# Motorcontroller.net
KiCad netlist of a schematic drawn in Altium Designer
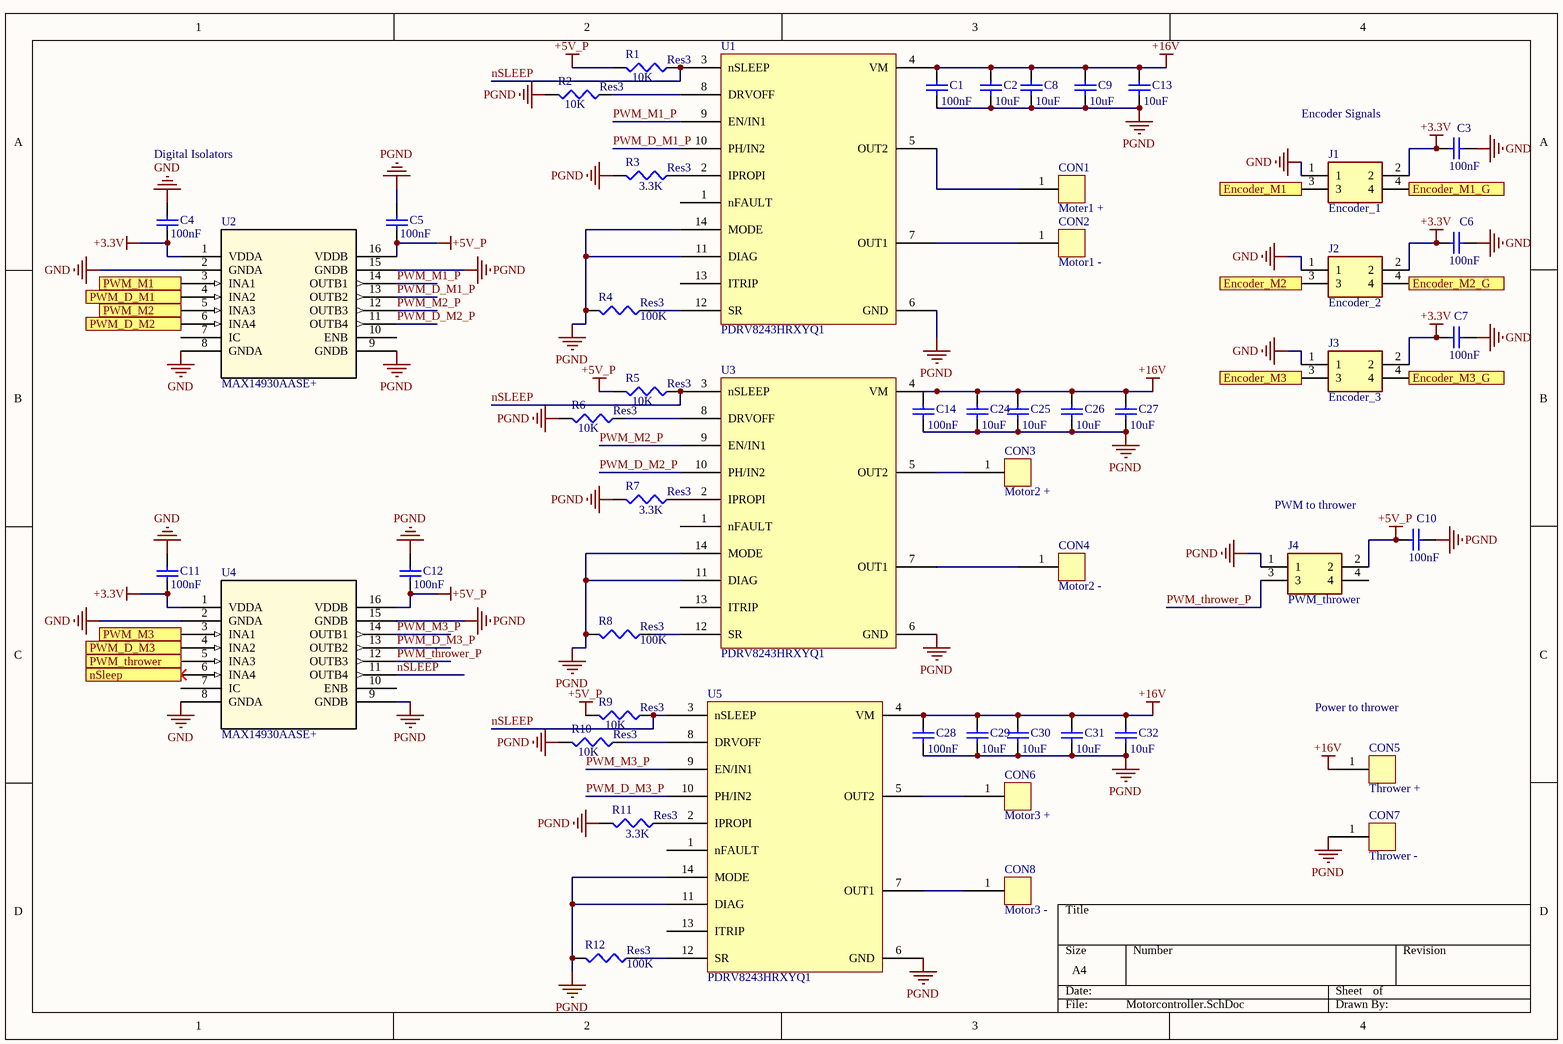
[diagram p0: Motorcontroller.SchDoc]

(export (version "E")
  (design (tool "Eeschema 10.0.6"))
  (components
    (comp (ref "C1")
      (value "100nF")
      (footprint "1608[0603]")
      (description "Capacitor (Semiconductor SIM Model)")
      (fields (field (name "Comment") "Cap Semi") (field (name "PUBLISHER") "Altium Limited"))
      (libsource (lib "Miscellaneous Devices") (part "Cap Semi"))
    )
    (comp (ref "C2")
      (value "10uF")
      (footprint "C1206")
      (description "Capacitor (Semiconductor SIM Model)")
      (fields (field (name "Comment") "Cap Semi") (field (name "PUBLISHER") "Altium Limited"))
      (libsource (lib "Miscellaneous Devices") (part "Cap Semi"))
    )
    (comp (ref "C3")
      (value "100nF")
      (footprint "1608[0603]")
      (description "Capacitor (Semiconductor SIM Model)")
      (fields (field (name "Comment") "Cap Semi") (field (name "PUBLISHER") "Altium Limited"))
      (libsource (lib "Miscellaneous Devices") (part "Cap Semi"))
    )
    (comp (ref "C4")
      (value "100nF")
      (footprint "1608[0603]")
      (description "Capacitor (Semiconductor SIM Model)")
      (fields (field (name "Comment") "Cap Semi") (field (name "PUBLISHER") "Altium Limited"))
      (libsource (lib "") (part "Cap Semi_1"))
    )
    (comp (ref "C5")
      (value "100nF")
      (footprint "1608[0603]")
      (description "Capacitor (Semiconductor SIM Model)")
      (fields (field (name "Comment") "Cap Semi") (field (name "PUBLISHER") "Altium Limited"))
      (libsource (lib "") (part "Cap Semi_1"))
    )
    (comp (ref "C6")
      (value "100nF")
      (footprint "1608[0603]")
      (description "Capacitor (Semiconductor SIM Model)")
      (fields (field (name "Comment") "Cap Semi") (field (name "PUBLISHER") "Altium Limited"))
      (libsource (lib "Miscellaneous Devices") (part "Cap Semi"))
    )
    (comp (ref "C7")
      (value "100nF")
      (footprint "1608[0603]")
      (description "Capacitor (Semiconductor SIM Model)")
      (fields (field (name "Comment") "Cap Semi") (field (name "PUBLISHER") "Altium Limited"))
      (libsource (lib "Miscellaneous Devices") (part "Cap Semi"))
    )
    (comp (ref "C8")
      (value "10uF")
      (footprint "C1206")
      (description "Capacitor (Semiconductor SIM Model)")
      (fields (field (name "Comment") "Cap Semi") (field (name "PUBLISHER") "Altium Limited"))
      (libsource (lib "Miscellaneous Devices") (part "Cap Semi"))
    )
    (comp (ref "C9")
      (value "10uF")
      (footprint "C1206")
      (description "Capacitor (Semiconductor SIM Model)")
      (fields (field (name "Comment") "Cap Semi") (field (name "PUBLISHER") "Altium Limited"))
      (libsource (lib "Miscellaneous Devices") (part "Cap Semi"))
    )
    (comp (ref "C10")
      (value "100nF")
      (footprint "1608[0603]")
      (description "Capacitor (Semiconductor SIM Model)")
      (fields (field (name "Comment") "Cap Semi") (field (name "PUBLISHER") "Altium Limited"))
      (libsource (lib "Miscellaneous Devices") (part "Cap Semi"))
    )
    (comp (ref "C11")
      (value "100nF")
      (footprint "1608[0603]")
      (description "Capacitor (Semiconductor SIM Model)")
      (fields (field (name "Comment") "Cap Semi") (field (name "PUBLISHER") "Altium Limited"))
      (libsource (lib "") (part "Cap Semi_1"))
    )
    (comp (ref "C12")
      (value "100nF")
      (footprint "1608[0603]")
      (description "Capacitor (Semiconductor SIM Model)")
      (fields (field (name "Comment") "Cap Semi") (field (name "PUBLISHER") "Altium Limited"))
      (libsource (lib "") (part "Cap Semi_1"))
    )
    (comp (ref "C13")
      (value "10uF")
      (footprint "C1206")
      (description "Capacitor (Semiconductor SIM Model)")
      (fields (field (name "Comment") "Cap Semi") (field (name "PUBLISHER") "Altium Limited"))
      (libsource (lib "Miscellaneous Devices") (part "Cap Semi"))
    )
    (comp (ref "C14")
      (value "100nF")
      (footprint "1608[0603]")
      (description "Capacitor (Semiconductor SIM Model)")
      (fields (field (name "Comment") "Cap Semi") (field (name "PUBLISHER") "Altium Limited"))
      (libsource (lib "Miscellaneous Devices") (part "Cap Semi"))
    )
    (comp (ref "C24")
      (value "10uF")
      (footprint "C1206")
      (description "Capacitor (Semiconductor SIM Model)")
      (fields (field (name "Comment") "Cap Semi") (field (name "PUBLISHER") "Altium Limited"))
      (libsource (lib "Miscellaneous Devices") (part "Cap Semi"))
    )
    (comp (ref "C25")
      (value "10uF")
      (footprint "C1206")
      (description "Capacitor (Semiconductor SIM Model)")
      (fields (field (name "Comment") "Cap Semi") (field (name "PUBLISHER") "Altium Limited"))
      (libsource (lib "Miscellaneous Devices") (part "Cap Semi"))
    )
    (comp (ref "C26")
      (value "10uF")
      (footprint "C1206")
      (description "Capacitor (Semiconductor SIM Model)")
      (fields (field (name "Comment") "Cap Semi") (field (name "PUBLISHER") "Altium Limited"))
      (libsource (lib "Miscellaneous Devices") (part "Cap Semi"))
    )
    (comp (ref "C27")
      (value "10uF")
      (footprint "C1206")
      (description "Capacitor (Semiconductor SIM Model)")
      (fields (field (name "Comment") "Cap Semi") (field (name "PUBLISHER") "Altium Limited"))
      (libsource (lib "Miscellaneous Devices") (part "Cap Semi"))
    )
    (comp (ref "C28")
      (value "100nF")
      (footprint "1608[0603]")
      (description "Capacitor (Semiconductor SIM Model)")
      (fields (field (name "Comment") "Cap Semi") (field (name "PUBLISHER") "Altium Limited"))
      (libsource (lib "Miscellaneous Devices") (part "Cap Semi"))
    )
    (comp (ref "C29")
      (value "10uF")
      (footprint "C1206")
      (description "Capacitor (Semiconductor SIM Model)")
      (fields (field (name "Comment") "Cap Semi") (field (name "PUBLISHER") "Altium Limited"))
      (libsource (lib "Miscellaneous Devices") (part "Cap Semi"))
    )
    (comp (ref "C30")
      (value "10uF")
      (footprint "C1206")
      (description "Capacitor (Semiconductor SIM Model)")
      (fields (field (name "Comment") "Cap Semi") (field (name "PUBLISHER") "Altium Limited"))
      (libsource (lib "Miscellaneous Devices") (part "Cap Semi"))
    )
    (comp (ref "C31")
      (value "10uF")
      (footprint "C1206")
      (description "Capacitor (Semiconductor SIM Model)")
      (fields (field (name "Comment") "Cap Semi") (field (name "PUBLISHER") "Altium Limited"))
      (libsource (lib "Miscellaneous Devices") (part "Cap Semi"))
    )
    (comp (ref "C32")
      (value "10uF")
      (footprint "C1206")
      (description "Capacitor (Semiconductor SIM Model)")
      (fields (field (name "Comment") "Cap Semi") (field (name "PUBLISHER") "Altium Limited"))
      (libsource (lib "Miscellaneous Devices") (part "Cap Semi"))
    )
    (comp (ref "CON1")
      (value "Moter1 +")
      (footprint "con_soldering")
      (libsource (lib "con_soldering") (part "Con_soldering"))
    )
    (comp (ref "CON2")
      (value "Motor1 -")
      (footprint "con_soldering")
      (libsource (lib "con_soldering") (part "Con_soldering"))
    )
    (comp (ref "CON3")
      (value "Motor2 +")
      (footprint "con_soldering")
      (libsource (lib "con_soldering") (part "Con_soldering"))
    )
    (comp (ref "CON4")
      (value "Motor2 -")
      (footprint "con_soldering")
      (libsource (lib "con_soldering") (part "Con_soldering"))
    )
    (comp (ref "CON5")
      (value "Thrower +")
      (footprint "con_soldering")
      (libsource (lib "con_soldering") (part "Con_soldering"))
    )
    (comp (ref "CON6")
      (value "Motor3 +")
      (footprint "con_soldering")
      (libsource (lib "con_soldering") (part "Con_soldering"))
    )
    (comp (ref "CON7")
      (value "Thrower -")
      (footprint "con_soldering")
      (libsource (lib "con_soldering") (part "Con_soldering"))
    )
    (comp (ref "CON8")
      (value "Motor3 -")
      (footprint "con_soldering")
      (libsource (lib "con_soldering") (part "Con_soldering"))
    )
    (comp (ref "J1")
      (value "Encoder_1")
      (footprint "TE_7-215079-4:TE_7-215079-4")
      (description "Micro-MaTch 4 Position 1.27 mm Pitch Vertical Female-on-Board Connector")
      (fields (field (name "MP") "7-215079-4") (field (name "MF") "TE Connectivity"))
      (libsource (lib "Con_encoder_4") (part "Con_4_encoder"))
    )
    (comp (ref "J2")
      (value "Encoder_2")
      (footprint "TE_7-215079-4:TE_7-215079-4")
      (description "Micro-MaTch 4 Position 1.27 mm Pitch Vertical Female-on-Board Connector")
      (fields (field (name "MP") "7-215079-4") (field (name "MF") "TE Connectivity"))
      (libsource (lib "Con_encoder_4") (part "Con_4_encoder"))
    )
    (comp (ref "J3")
      (value "Encoder_3")
      (footprint "TE_7-215079-4:TE_7-215079-4")
      (description "Micro-MaTch 4 Position 1.27 mm Pitch Vertical Female-on-Board Connector")
      (fields (field (name "MP") "7-215079-4") (field (name "MF") "TE Connectivity"))
      (libsource (lib "Con_encoder_4") (part "Con_4_encoder"))
    )
    (comp (ref "J4")
      (value "PWM_thrower")
      (footprint "TE_7-215079-4:TE_7-215079-4")
      (description "Micro-MaTch 4 Position 1.27 mm Pitch Vertical Female-on-Board Connector")
      (fields (field (name "MP") "7-215079-4") (field (name "MF") "TE Connectivity"))
      (libsource (lib "Con_encoder_4") (part "Con_4_encoder"))
    )
    (comp (ref "R1")
      (value "Res3")
      (footprint "J1-0603")
      (description "Resistor")
      (fields (field (name "ALTIUM_VALUE") "10K") (field (name "PUBLISHER") "Altium Limited"))
      (libsource (lib "Miscellaneous Devices") (part "Res3"))
    )
    (comp (ref "R2")
      (value "Res3")
      (footprint "J1-0603")
      (description "Resistor")
      (fields (field (name "ALTIUM_VALUE") "10K") (field (name "PUBLISHER") "Altium Limited"))
      (libsource (lib "Miscellaneous Devices") (part "Res3"))
    )
    (comp (ref "R3")
      (value "Res3")
      (footprint "J1-0603")
      (description "Resistor")
      (fields (field (name "ALTIUM_VALUE") "3.3K") (field (name "PUBLISHER") "Altium Limited"))
      (libsource (lib "Miscellaneous Devices") (part "Res3"))
    )
    (comp (ref "R4")
      (value "Res3")
      (footprint "J1-0603")
      (description "Resistor")
      (fields (field (name "ALTIUM_VALUE") "100K") (field (name "PUBLISHER") "Altium Limited"))
      (libsource (lib "Miscellaneous Devices") (part "Res3"))
    )
    (comp (ref "R5")
      (value "Res3")
      (footprint "J1-0603")
      (description "Resistor")
      (fields (field (name "ALTIUM_VALUE") "10K") (field (name "PUBLISHER") "Altium Limited"))
      (libsource (lib "Miscellaneous Devices") (part "Res3"))
    )
    (comp (ref "R6")
      (value "Res3")
      (footprint "J1-0603")
      (description "Resistor")
      (fields (field (name "ALTIUM_VALUE") "10K") (field (name "PUBLISHER") "Altium Limited"))
      (libsource (lib "Miscellaneous Devices") (part "Res3"))
    )
    (comp (ref "R7")
      (value "Res3")
      (footprint "J1-0603")
      (description "Resistor")
      (fields (field (name "ALTIUM_VALUE") "3.3K") (field (name "PUBLISHER") "Altium Limited"))
      (libsource (lib "Miscellaneous Devices") (part "Res3"))
    )
    (comp (ref "R8")
      (value "Res3")
      (footprint "J1-0603")
      (description "Resistor")
      (fields (field (name "ALTIUM_VALUE") "100K") (field (name "PUBLISHER") "Altium Limited"))
      (libsource (lib "Miscellaneous Devices") (part "Res3"))
    )
    (comp (ref "R9")
      (value "Res3")
      (footprint "J1-0603")
      (description "Resistor")
      (fields (field (name "ALTIUM_VALUE") "10K") (field (name "PUBLISHER") "Altium Limited"))
      (libsource (lib "Miscellaneous Devices") (part "Res3"))
    )
    (comp (ref "R10")
      (value "Res3")
      (footprint "J1-0603")
      (description "Resistor")
      (fields (field (name "ALTIUM_VALUE") "10K") (field (name "PUBLISHER") "Altium Limited"))
      (libsource (lib "Miscellaneous Devices") (part "Res3"))
    )
    (comp (ref "R11")
      (value "Res3")
      (footprint "J1-0603")
      (description "Resistor")
      (fields (field (name "ALTIUM_VALUE") "3.3K") (field (name "PUBLISHER") "Altium Limited"))
      (libsource (lib "Miscellaneous Devices") (part "Res3"))
    )
    (comp (ref "R12")
      (value "Res3")
      (footprint "J1-0603")
      (description "Resistor")
      (fields (field (name "ALTIUM_VALUE") "100K") (field (name "PUBLISHER") "Altium Limited"))
      (libsource (lib "Miscellaneous Devices") (part "Res3"))
    )
    (comp (ref "U1")
      (value "PDRV8243HRXYQ1")
      (footprint "DRV8243_motor_driver")
      (libsource (lib "DRV8243-Q1") (part "PDRV8243HRXYQ1"))
    )
    (comp (ref "U2")
      (value "MAX14930AASE+")
      (footprint "21-0041_S16+1_MXM")
      (description "No Description Available")
      (fields (field (name "COPYRIGHT") "Copyright (C) 2021 Ultra Librarian. All rights reserved."))
      (libsource (lib "MAX14930AASE&plus_") (part "MAX14930AASE+"))
    )
    (comp (ref "U3")
      (value "PDRV8243HRXYQ1")
      (footprint "DRV8243_motor_driver")
      (libsource (lib "DRV8243-Q1") (part "PDRV8243HRXYQ1"))
    )
    (comp (ref "U4")
      (value "MAX14930AASE+")
      (footprint "21-0041_S16+1_MXM")
      (description "No Description Available")
      (fields (field (name "COPYRIGHT") "Copyright (C) 2021 Ultra Librarian. All rights reserved."))
      (libsource (lib "MAX14930AASE&plus_") (part "MAX14930AASE+"))
    )
    (comp (ref "U5")
      (value "PDRV8243HRXYQ1")
      (footprint "DRV8243_motor_driver")
      (libsource (lib "DRV8243-Q1") (part "PDRV8243HRXYQ1"))
    )
  )
  (nets
    (net (code "1") (name "+3.3V") (class "Default")
      (node (ref "C11") (pin "2") (pinfunction "2_2") (pintype "passive"))
      (node (ref "C3") (pin "2") (pinfunction "2_2") (pintype "passive"))
      (node (ref "C4") (pin "2") (pinfunction "2_2") (pintype "passive"))
      (node (ref "C6") (pin "2") (pinfunction "2_2") (pintype "passive"))
      (node (ref "C7") (pin "2") (pinfunction "2_2") (pintype "passive"))
      (node (ref "J1") (pin "2") (pinfunction "2_2") (pintype "passive"))
      (node (ref "J2") (pin "2") (pinfunction "2_2") (pintype "passive"))
      (node (ref "J3") (pin "2") (pinfunction "2_2") (pintype "passive"))
      (node (ref "U2") (pin "1") (pinfunction "VDDA_1") (pintype "power_in"))
      (node (ref "U4") (pin "1") (pinfunction "VDDA_1") (pintype "power_in"))
    )
    (net (code "2") (name "+5V_P") (class "Default")
      (node (ref "C10") (pin "2") (pinfunction "2_2") (pintype "passive"))
      (node (ref "C12") (pin "2") (pinfunction "2_2") (pintype "passive"))
      (node (ref "C5") (pin "2") (pinfunction "2_2") (pintype "passive"))
      (node (ref "J4") (pin "2") (pinfunction "2_2") (pintype "passive"))
      (node (ref "R1") (pin "2") (pinfunction "2_2") (pintype "passive"))
      (node (ref "R5") (pin "2") (pinfunction "2_2") (pintype "passive"))
      (node (ref "R9") (pin "2") (pinfunction "2_2") (pintype "passive"))
      (node (ref "U2") (pin "16") (pinfunction "VDDB_16") (pintype "power_in"))
      (node (ref "U4") (pin "16") (pinfunction "VDDB_16") (pintype "power_in"))
    )
    (net (code "3") (name "+16V") (class "Default")
      (node (ref "C1") (pin "2") (pinfunction "2_2") (pintype "passive"))
      (node (ref "C13") (pin "2") (pinfunction "2_2") (pintype "passive"))
      (node (ref "C14") (pin "2") (pinfunction "2_2") (pintype "passive"))
      (node (ref "C2") (pin "2") (pinfunction "2_2") (pintype "passive"))
      (node (ref "C24") (pin "2") (pinfunction "2_2") (pintype "passive"))
      (node (ref "C25") (pin "2") (pinfunction "2_2") (pintype "passive"))
      (node (ref "C26") (pin "2") (pinfunction "2_2") (pintype "passive"))
      (node (ref "C27") (pin "2") (pinfunction "2_2") (pintype "passive"))
      (node (ref "C28") (pin "2") (pinfunction "2_2") (pintype "passive"))
      (node (ref "C29") (pin "2") (pinfunction "2_2") (pintype "passive"))
      (node (ref "C30") (pin "2") (pinfunction "2_2") (pintype "passive"))
      (node (ref "C31") (pin "2") (pinfunction "2_2") (pintype "passive"))
      (node (ref "C32") (pin "2") (pinfunction "2_2") (pintype "passive"))
      (node (ref "C8") (pin "2") (pinfunction "2_2") (pintype "passive"))
      (node (ref "C9") (pin "2") (pinfunction "2_2") (pintype "passive"))
      (node (ref "CON5") (pin "1") (pintype "passive"))
      (node (ref "U1") (pin "4") (pinfunction "VM_4") (pintype "passive"))
      (node (ref "U3") (pin "4") (pinfunction "VM_4") (pintype "passive"))
      (node (ref "U5") (pin "4") (pinfunction "VM_4") (pintype "passive"))
    )
    (net (code "4") (name "/Encoder_M1") (class "Default")
      (node (ref "J1") (pin "3") (pinfunction "3_3") (pintype "passive"))
    )
    (net (code "5") (name "/Encoder_M1_G") (class "Default")
      (node (ref "J1") (pin "4") (pinfunction "4_4") (pintype "passive"))
    )
    (net (code "6") (name "/Encoder_M2") (class "Default")
      (node (ref "J2") (pin "3") (pinfunction "3_3") (pintype "passive"))
    )
    (net (code "7") (name "/Encoder_M2_G") (class "Default")
      (node (ref "J2") (pin "4") (pinfunction "4_4") (pintype "passive"))
    )
    (net (code "8") (name "/Encoder_M3") (class "Default")
      (node (ref "J3") (pin "3") (pinfunction "3_3") (pintype "passive"))
    )
    (net (code "9") (name "/Encoder_M3_G") (class "Default")
      (node (ref "J3") (pin "4") (pinfunction "4_4") (pintype "passive"))
    )
    (net (code "10") (name "/PWM_D_M1") (class "Default")
      (node (ref "U2") (pin "4") (pinfunction "INA2_4") (pintype "input"))
    )
    (net (code "11") (name "/PWM_D_M1_P") (class "Default")
      (node (ref "U1") (pin "10") (pinfunction "PH/IN2_10") (pintype "passive"))
      (node (ref "U2") (pin "13") (pinfunction "OUTB2_13") (pintype "output"))
    )
    (net (code "12") (name "/PWM_D_M2") (class "Default")
      (node (ref "U2") (pin "6") (pinfunction "INA4_6") (pintype "input"))
    )
    (net (code "13") (name "/PWM_D_M2_P") (class "Default")
      (node (ref "U2") (pin "11") (pinfunction "OUTB4_11") (pintype "output"))
      (node (ref "U3") (pin "10") (pinfunction "PH/IN2_10") (pintype "passive"))
    )
    (net (code "14") (name "/PWM_D_M3") (class "Default")
      (node (ref "U4") (pin "4") (pinfunction "INA2_4") (pintype "input"))
    )
    (net (code "15") (name "/PWM_D_M3_P") (class "Default")
      (node (ref "U4") (pin "13") (pinfunction "OUTB2_13") (pintype "output"))
      (node (ref "U5") (pin "10") (pinfunction "PH/IN2_10") (pintype "passive"))
    )
    (net (code "16") (name "/PWM_M1") (class "Default")
      (node (ref "U2") (pin "3") (pinfunction "INA1_3") (pintype "input"))
    )
    (net (code "17") (name "/PWM_M1_P") (class "Default")
      (node (ref "U1") (pin "9") (pinfunction "EN/IN1_9") (pintype "passive"))
      (node (ref "U2") (pin "14") (pinfunction "OUTB1_14") (pintype "output"))
    )
    (net (code "18") (name "/PWM_M2") (class "Default")
      (node (ref "U2") (pin "5") (pinfunction "INA3_5") (pintype "input"))
    )
    (net (code "19") (name "/PWM_M2_P") (class "Default")
      (node (ref "U2") (pin "12") (pinfunction "OUTB3_12") (pintype "output"))
      (node (ref "U3") (pin "9") (pinfunction "EN/IN1_9") (pintype "passive"))
    )
    (net (code "20") (name "/PWM_M3") (class "Default")
      (node (ref "U4") (pin "3") (pinfunction "INA1_3") (pintype "input"))
    )
    (net (code "21") (name "/PWM_M3_P") (class "Default")
      (node (ref "U4") (pin "14") (pinfunction "OUTB1_14") (pintype "output"))
      (node (ref "U5") (pin "9") (pinfunction "EN/IN1_9") (pintype "passive"))
    )
    (net (code "22") (name "/PWM_thrower") (class "Default")
      (node (ref "U4") (pin "5") (pinfunction "INA3_5") (pintype "input"))
    )
    (net (code "23") (name "/PWM_thrower_P") (class "Default")
      (node (ref "J4") (pin "3") (pinfunction "3_3") (pintype "passive"))
      (node (ref "U4") (pin "12") (pinfunction "OUTB3_12") (pintype "output"))
    )
    (net (code "24") (name "/nSLEEP") (class "Default")
      (node (ref "R1") (pin "1") (pinfunction "1_1") (pintype "passive"))
      (node (ref "R5") (pin "1") (pinfunction "1_1") (pintype "passive"))
      (node (ref "R9") (pin "1") (pinfunction "1_1") (pintype "passive"))
      (node (ref "U1") (pin "3") (pinfunction "nSLEEP_3") (pintype "passive"))
      (node (ref "U3") (pin "3") (pinfunction "nSLEEP_3") (pintype "passive"))
      (node (ref "U4") (pin "11") (pinfunction "OUTB4_11") (pintype "output"))
      (node (ref "U5") (pin "3") (pinfunction "nSLEEP_3") (pintype "passive"))
    )
    (net (code "25") (name "/nSleep") (class "Default")
      (node (ref "U4") (pin "6") (pinfunction "INA4_6") (pintype "input+no_connect"))
    )
    (net (code "26") (name "GND") (class "Default")
      (node (ref "C11") (pin "1") (pinfunction "1_1") (pintype "passive"))
      (node (ref "C3") (pin "1") (pinfunction "1_1") (pintype "passive"))
      (node (ref "C4") (pin "1") (pinfunction "1_1") (pintype "passive"))
      (node (ref "C6") (pin "1") (pinfunction "1_1") (pintype "passive"))
      (node (ref "C7") (pin "1") (pinfunction "1_1") (pintype "passive"))
      (node (ref "J1") (pin "1") (pinfunction "1_1") (pintype "passive"))
      (node (ref "J2") (pin "1") (pinfunction "1_1") (pintype "passive"))
      (node (ref "J3") (pin "1") (pinfunction "1_1") (pintype "passive"))
      (node (ref "U2") (pin "2") (pinfunction "GNDA_2") (pintype "power_in"))
      (node (ref "U2") (pin "8") (pinfunction "GNDA_8") (pintype "power_in"))
      (node (ref "U4") (pin "2") (pinfunction "GNDA_2") (pintype "power_in"))
      (node (ref "U4") (pin "8") (pinfunction "GNDA_8") (pintype "power_in"))
    )
    (net (code "27") (name "Net-(U1-DRVOFF)") (class "Default")
      (node (ref "R2") (pin "1") (pinfunction "1_1") (pintype "passive"))
      (node (ref "U1") (pin "8") (pinfunction "DRVOFF_8") (pintype "passive"))
    )
    (net (code "28") (name "Net-(U1-IPROPI)") (class "Default")
      (node (ref "R3") (pin "1") (pinfunction "1_1") (pintype "passive"))
      (node (ref "U1") (pin "2") (pinfunction "IPROPI_2") (pintype "passive"))
    )
    (net (code "29") (name "Net-(U1-OUT1)") (class "Default")
      (node (ref "CON2") (pin "1") (pintype "passive"))
      (node (ref "U1") (pin "7") (pinfunction "OUT1_7") (pintype "passive"))
    )
    (net (code "30") (name "Net-(U1-OUT2)") (class "Default")
      (node (ref "CON1") (pin "1") (pintype "passive"))
      (node (ref "U1") (pin "5") (pinfunction "OUT2_5") (pintype "passive"))
    )
    (net (code "31") (name "Net-(U1-SR)") (class "Default")
      (node (ref "R4") (pin "1") (pinfunction "1_1") (pintype "passive"))
      (node (ref "U1") (pin "12") (pinfunction "SR_12") (pintype "passive"))
    )
    (net (code "32") (name "Net-(U3-DRVOFF)") (class "Default")
      (node (ref "R6") (pin "1") (pinfunction "1_1") (pintype "passive"))
      (node (ref "U3") (pin "8") (pinfunction "DRVOFF_8") (pintype "passive"))
    )
    (net (code "33") (name "Net-(U3-IPROPI)") (class "Default")
      (node (ref "R7") (pin "1") (pinfunction "1_1") (pintype "passive"))
      (node (ref "U3") (pin "2") (pinfunction "IPROPI_2") (pintype "passive"))
    )
    (net (code "34") (name "Net-(U3-OUT1)") (class "Default")
      (node (ref "CON4") (pin "1") (pintype "passive"))
      (node (ref "U3") (pin "7") (pinfunction "OUT1_7") (pintype "passive"))
    )
    (net (code "35") (name "Net-(U3-OUT2)") (class "Default")
      (node (ref "CON3") (pin "1") (pintype "passive"))
      (node (ref "U3") (pin "5") (pinfunction "OUT2_5") (pintype "passive"))
    )
    (net (code "36") (name "Net-(U3-SR)") (class "Default")
      (node (ref "R8") (pin "1") (pinfunction "1_1") (pintype "passive"))
      (node (ref "U3") (pin "12") (pinfunction "SR_12") (pintype "passive"))
    )
    (net (code "37") (name "Net-(U5-DRVOFF)") (class "Default")
      (node (ref "R10") (pin "1") (pinfunction "1_1") (pintype "passive"))
      (node (ref "U5") (pin "8") (pinfunction "DRVOFF_8") (pintype "passive"))
    )
    (net (code "38") (name "Net-(U5-IPROPI)") (class "Default")
      (node (ref "R11") (pin "1") (pinfunction "1_1") (pintype "passive"))
      (node (ref "U5") (pin "2") (pinfunction "IPROPI_2") (pintype "passive"))
    )
    (net (code "39") (name "Net-(U5-OUT1)") (class "Default")
      (node (ref "CON8") (pin "1") (pintype "passive"))
      (node (ref "U5") (pin "7") (pinfunction "OUT1_7") (pintype "passive"))
    )
    (net (code "40") (name "Net-(U5-OUT2)") (class "Default")
      (node (ref "CON6") (pin "1") (pintype "passive"))
      (node (ref "U5") (pin "5") (pinfunction "OUT2_5") (pintype "passive"))
    )
    (net (code "41") (name "Net-(U5-SR)") (class "Default")
      (node (ref "R12") (pin "1") (pinfunction "1_1") (pintype "passive"))
      (node (ref "U5") (pin "12") (pinfunction "SR_12") (pintype "passive"))
    )
    (net (code "42") (name "PGND") (class "Default")
      (node (ref "C1") (pin "1") (pinfunction "1_1") (pintype "passive"))
      (node (ref "C10") (pin "1") (pinfunction "1_1") (pintype "passive"))
      (node (ref "C12") (pin "1") (pinfunction "1_1") (pintype "passive"))
      (node (ref "C13") (pin "1") (pinfunction "1_1") (pintype "passive"))
      (node (ref "C14") (pin "1") (pinfunction "1_1") (pintype "passive"))
      (node (ref "C2") (pin "1") (pinfunction "1_1") (pintype "passive"))
      (node (ref "C24") (pin "1") (pinfunction "1_1") (pintype "passive"))
      (node (ref "C25") (pin "1") (pinfunction "1_1") (pintype "passive"))
      (node (ref "C26") (pin "1") (pinfunction "1_1") (pintype "passive"))
      (node (ref "C27") (pin "1") (pinfunction "1_1") (pintype "passive"))
      (node (ref "C28") (pin "1") (pinfunction "1_1") (pintype "passive"))
      (node (ref "C29") (pin "1") (pinfunction "1_1") (pintype "passive"))
      (node (ref "C30") (pin "1") (pinfunction "1_1") (pintype "passive"))
      (node (ref "C31") (pin "1") (pinfunction "1_1") (pintype "passive"))
      (node (ref "C32") (pin "1") (pinfunction "1_1") (pintype "passive"))
      (node (ref "C5") (pin "1") (pinfunction "1_1") (pintype "passive"))
      (node (ref "C8") (pin "1") (pinfunction "1_1") (pintype "passive"))
      (node (ref "C9") (pin "1") (pinfunction "1_1") (pintype "passive"))
      (node (ref "CON7") (pin "1") (pintype "passive"))
      (node (ref "J4") (pin "1") (pinfunction "1_1") (pintype "passive"))
      (node (ref "R10") (pin "2") (pinfunction "2_2") (pintype "passive"))
      (node (ref "R11") (pin "2") (pinfunction "2_2") (pintype "passive"))
      (node (ref "R12") (pin "2") (pinfunction "2_2") (pintype "passive"))
      (node (ref "R2") (pin "2") (pinfunction "2_2") (pintype "passive"))
      (node (ref "R3") (pin "2") (pinfunction "2_2") (pintype "passive"))
      (node (ref "R4") (pin "2") (pinfunction "2_2") (pintype "passive"))
      (node (ref "R6") (pin "2") (pinfunction "2_2") (pintype "passive"))
      (node (ref "R7") (pin "2") (pinfunction "2_2") (pintype "passive"))
      (node (ref "R8") (pin "2") (pinfunction "2_2") (pintype "passive"))
      (node (ref "U1") (pin "11") (pinfunction "DIAG_11") (pintype "passive"))
      (node (ref "U1") (pin "14") (pinfunction "MODE_14") (pintype "passive"))
      (node (ref "U1") (pin "6") (pinfunction "GND_6") (pintype "passive"))
      (node (ref "U2") (pin "15") (pinfunction "GNDB_15") (pintype "power_in"))
      (node (ref "U2") (pin "9") (pinfunction "GNDB_9") (pintype "power_in"))
      (node (ref "U3") (pin "11") (pinfunction "DIAG_11") (pintype "passive"))
      (node (ref "U3") (pin "14") (pinfunction "MODE_14") (pintype "passive"))
      (node (ref "U3") (pin "6") (pinfunction "GND_6") (pintype "passive"))
      (node (ref "U4") (pin "15") (pinfunction "GNDB_15") (pintype "power_in"))
      (node (ref "U4") (pin "9") (pinfunction "GNDB_9") (pintype "power_in"))
      (node (ref "U5") (pin "11") (pinfunction "DIAG_11") (pintype "passive"))
      (node (ref "U5") (pin "14") (pinfunction "MODE_14") (pintype "passive"))
      (node (ref "U5") (pin "6") (pinfunction "GND_6") (pintype "passive"))
    )
    (net (code "43") (name "unconnected-(J4-Pad4)") (class "Default")
      (node (ref "J4") (pin "4") (pinfunction "4_4") (pintype "passive"))
    )
    (net (code "44") (name "unconnected-(U1-ITRIP-Pad13)") (class "Default")
      (node (ref "U1") (pin "13") (pinfunction "ITRIP_13") (pintype "passive"))
    )
    (net (code "45") (name "unconnected-(U1-nFAULT-Pad1)") (class "Default")
      (node (ref "U1") (pin "1") (pinfunction "nFAULT_1") (pintype "passive"))
    )
    (net (code "46") (name "unconnected-(U2-ENB-Pad10)") (class "Default")
      (node (ref "U2") (pin "10") (pinfunction "ENB_10") (pintype "passive"))
    )
    (net (code "47") (name "unconnected-(U2-IC-Pad7)") (class "Default")
      (node (ref "U2") (pin "7") (pinfunction "IC_7") (pintype "passive"))
    )
    (net (code "48") (name "unconnected-(U3-ITRIP-Pad13)") (class "Default")
      (node (ref "U3") (pin "13") (pinfunction "ITRIP_13") (pintype "passive"))
    )
    (net (code "49") (name "unconnected-(U3-nFAULT-Pad1)") (class "Default")
      (node (ref "U3") (pin "1") (pinfunction "nFAULT_1") (pintype "passive"))
    )
    (net (code "50") (name "unconnected-(U4-ENB-Pad10)") (class "Default")
      (node (ref "U4") (pin "10") (pinfunction "ENB_10") (pintype "passive"))
    )
    (net (code "51") (name "unconnected-(U4-IC-Pad7)") (class "Default")
      (node (ref "U4") (pin "7") (pinfunction "IC_7") (pintype "passive"))
    )
    (net (code "52") (name "unconnected-(U5-ITRIP-Pad13)") (class "Default")
      (node (ref "U5") (pin "13") (pinfunction "ITRIP_13") (pintype "passive"))
    )
    (net (code "53") (name "unconnected-(U5-nFAULT-Pad1)") (class "Default")
      (node (ref "U5") (pin "1") (pinfunction "nFAULT_1") (pintype "passive"))
    )
  )
)
